# Boost.net
KiCad netlist of a schematic drawn in Altium Designer
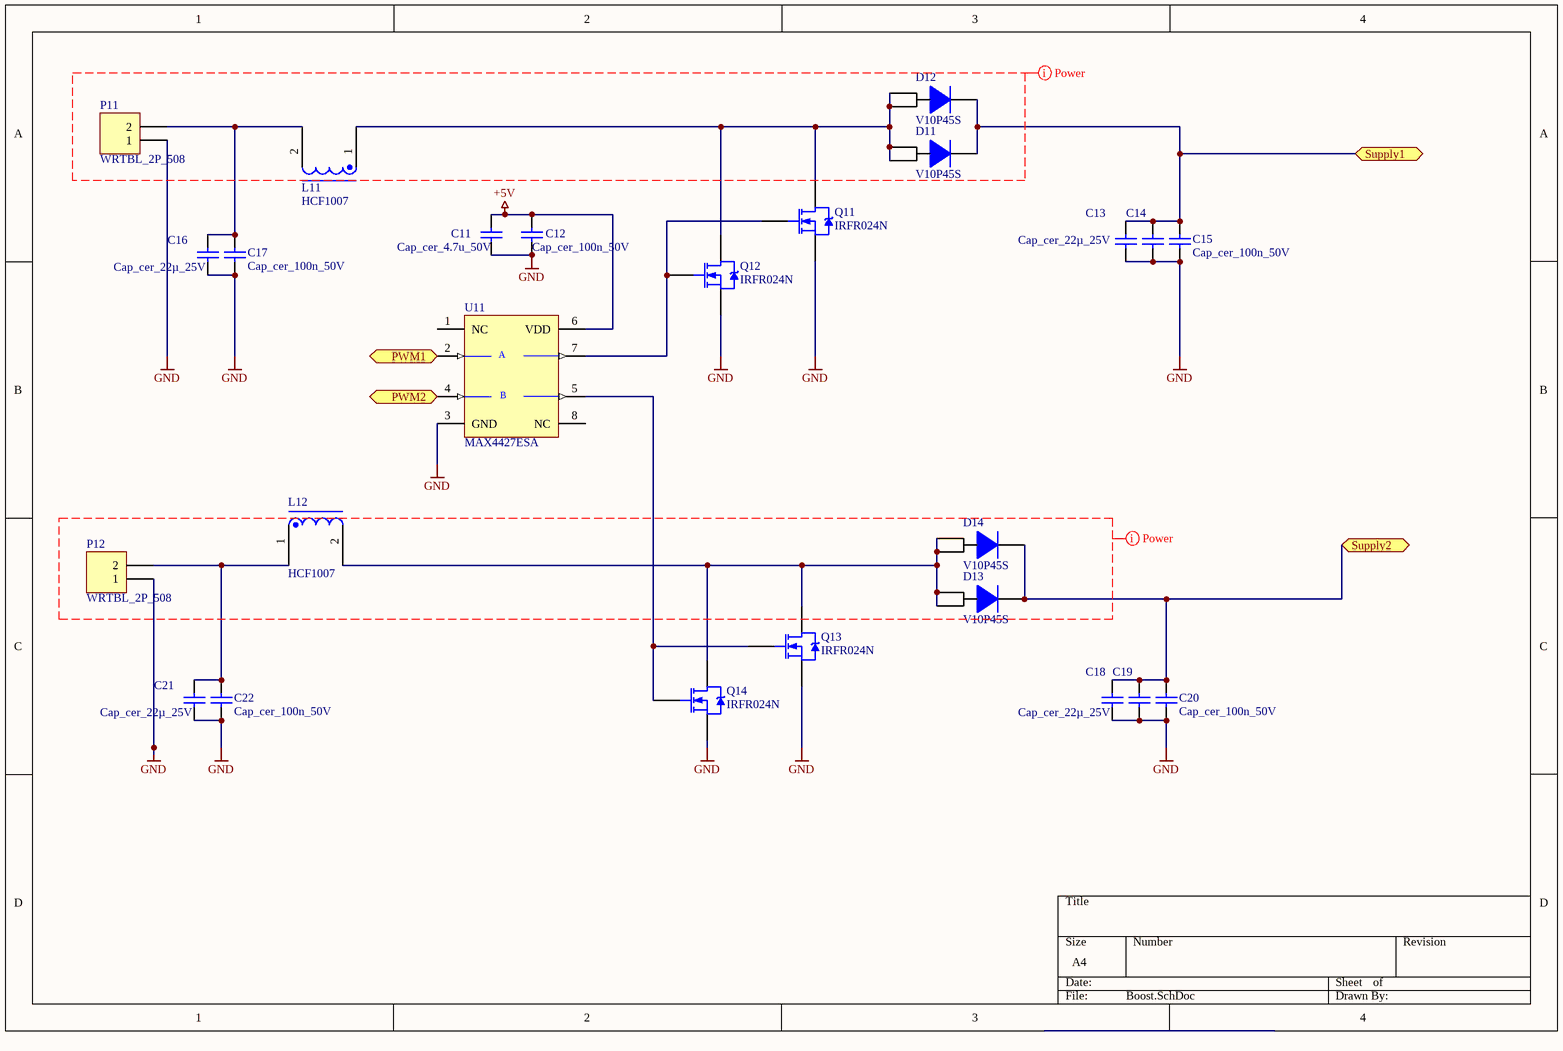
[diagram p0: Boost.SchDoc]

(export (version "E")
  (design (tool "Eeschema 10.0.6"))
  (components
    (comp (ref "C11")
      (value "Cap_cer_4.7u_50V")
      (footprint "_0805")
      (fields (field (name "VOLTAGE") "50V"))
      (libsource (lib "Capacitors$") (part "Cap_124"))
    )
    (comp (ref "C12")
      (value "Cap_cer_100n_50V")
      (footprint "_0805")
      (fields (field (name "VOLTAGE") "50V"))
      (libsource (lib "Capacitors$") (part "Cap_124"))
    )
    (comp (ref "C13")
      (value "~")
      (footprint "_0805")
      (fields (field (name "VOLTAGE") "25V"))
      (libsource (lib "Capacitors$") (part "Cap_124"))
    )
    (comp (ref "C14")
      (value "Cap_cer_22µ_25V")
      (footprint "_0805")
      (fields (field (name "VOLTAGE") "25V"))
      (libsource (lib "Capacitors$") (part "Cap_124"))
    )
    (comp (ref "C15")
      (value "Cap_cer_100n_50V")
      (footprint "_0805")
      (fields (field (name "VOLTAGE") "50V"))
      (libsource (lib "Capacitors$") (part "Cap_124"))
    )
    (comp (ref "C16")
      (value "Cap_cer_22µ_25V")
      (footprint "_0805")
      (fields (field (name "VOLTAGE") "25V"))
      (libsource (lib "Capacitors$") (part "Cap_124"))
    )
    (comp (ref "C17")
      (value "Cap_cer_100n_50V")
      (footprint "_0805")
      (fields (field (name "VOLTAGE") "50V"))
      (libsource (lib "Capacitors$") (part "Cap_124"))
    )
    (comp (ref "C18")
      (value "Cap_cer_22µ_25V")
      (footprint "_0805")
      (fields (field (name "VOLTAGE") "25V"))
      (libsource (lib "Capacitors$") (part "Cap_124"))
    )
    (comp (ref "C19")
      (value "Cap_cer_22µ_25V")
      (footprint "_0805")
      (fields (field (name "VOLTAGE") "25V"))
      (libsource (lib "Capacitors$") (part "Cap_124"))
    )
    (comp (ref "C20")
      (value "Cap_cer_100n_50V")
      (footprint "_0805")
      (fields (field (name "VOLTAGE") "50V"))
      (libsource (lib "Capacitors$") (part "Cap_124"))
    )
    (comp (ref "C21")
      (value "Cap_cer_22µ_25V")
      (footprint "_0805")
      (fields (field (name "VOLTAGE") "25V"))
      (libsource (lib "Capacitors$") (part "Cap_124"))
    )
    (comp (ref "C22")
      (value "Cap_cer_100n_50V")
      (footprint "_0805")
      (fields (field (name "VOLTAGE") "50V"))
      (libsource (lib "Capacitors$") (part "Cap_124"))
    )
    (comp (ref "D11")
      (value "V10P45S")
      (footprint "TO-277A")
      (description "V01P45 Shottky Diode")
      (libsource (lib "Project_Components") (part "V10P45S"))
    )
    (comp (ref "D12")
      (value "V10P45S")
      (footprint "TO-277A")
      (description "V01P45 Shottky Diode")
      (libsource (lib "Project_Components") (part "V10P45S"))
    )
    (comp (ref "D13")
      (value "V10P45S")
      (footprint "TO-277A")
      (description "V01P45 Shottky Diode")
      (libsource (lib "Project_Components") (part "V10P45S"))
    )
    (comp (ref "D14")
      (value "V10P45S")
      (footprint "TO-277A")
      (description "V01P45 Shottky Diode")
      (libsource (lib "Project_Components") (part "V10P45S"))
    )
    (comp (ref "L11")
      (value "HCF1007")
      (footprint "HCF1007")
      (description "HCF1007 Inductor")
      (libsource (lib "Project_Components") (part "HCF1007"))
    )
    (comp (ref "L12")
      (value "HCF1007")
      (footprint "HCF1007")
      (description "HCF1007 Inductor")
      (libsource (lib "Project_Components") (part "HCF1007"))
    )
    (comp (ref "P11")
      (value "WRTBL_2P_508")
      (footprint "WRTBL_2P_508")
      (libsource (lib "Connectors$") (part "Con_7"))
    )
    (comp (ref "P12")
      (value "WRTBL_2P_508")
      (footprint "WRTBL_2P_508")
      (libsource (lib "Connectors$") (part "Con_7"))
    )
    (comp (ref "Q11")
      (value "IRFR024N")
      (footprint "TO-252AA_N")
      (description "HEXFET N-Channel Power MOSFET")
      (fields (field (name "PUBLISHER") "Altium Limited"))
      (libsource (lib "IR Discrete MOSFET - Power") (part "IRFR024N"))
    )
    (comp (ref "Q12")
      (value "IRFR024N")
      (footprint "TO-252AA_N")
      (description "HEXFET N-Channel Power MOSFET")
      (fields (field (name "PUBLISHER") "Altium Limited"))
      (libsource (lib "IR Discrete MOSFET - Power") (part "IRFR024N"))
    )
    (comp (ref "Q13")
      (value "IRFR024N")
      (footprint "TO-252AA_N")
      (description "HEXFET N-Channel Power MOSFET")
      (fields (field (name "PUBLISHER") "Altium Limited"))
      (libsource (lib "IR Discrete MOSFET - Power") (part "IRFR024N"))
    )
    (comp (ref "Q14")
      (value "IRFR024N")
      (footprint "TO-252AA_N")
      (description "HEXFET N-Channel Power MOSFET")
      (fields (field (name "PUBLISHER") "Altium Limited"))
      (libsource (lib "IR Discrete MOSFET - Power") (part "IRFR024N"))
    )
    (comp (ref "U11")
      (value "MAX4427ESA")
      (footprint "NSO8_N")
      (description "Dual High-Speed 1.5A MOSFET Driver")
      (fields (field (name "PUBLISHER") "Altium Limited"))
      (libsource (lib "Maxim Interface MOSFET Driver") (part "MAX4427ESA"))
    )
  )
  (nets
    (net (code "1") (name "+5V") (class "Default")
      (node (ref "C11") (pin "2") (pinfunction "2_2") (pintype "passive"))
      (node (ref "C12") (pin "2") (pinfunction "2_2") (pintype "passive"))
      (node (ref "U11") (pin "6") (pinfunction "VDD_6") (pintype "power_in"))
    )
    (net (code "2") (name "/PWM1") (class "Default")
      (node (ref "U11") (pin "2") (pinfunction "INA_2") (pintype "input"))
    )
    (net (code "3") (name "/PWM2") (class "Default")
      (node (ref "U11") (pin "4") (pinfunction "INB_4") (pintype "input"))
    )
    (net (code "4") (name "/Supply1") (class "Default")
      (node (ref "C13") (pin "2") (pinfunction "2_2") (pintype "passive"))
      (node (ref "C14") (pin "2") (pinfunction "2_2") (pintype "passive"))
      (node (ref "C15") (pin "2") (pinfunction "2_2") (pintype "passive"))
      (node (ref "D11") (pin "K") (pinfunction "K_K") (pintype "passive"))
      (node (ref "D12") (pin "K") (pinfunction "K_K") (pintype "passive"))
    )
    (net (code "5") (name "/Supply2") (class "Default")
      (node (ref "C18") (pin "2") (pinfunction "2_2") (pintype "passive"))
      (node (ref "C19") (pin "2") (pinfunction "2_2") (pintype "passive"))
      (node (ref "C20") (pin "2") (pinfunction "2_2") (pintype "passive"))
      (node (ref "D13") (pin "K") (pinfunction "K_K") (pintype "passive"))
      (node (ref "D14") (pin "K") (pinfunction "K_K") (pintype "passive"))
    )
    (net (code "6") (name "GND") (class "Default")
      (node (ref "C11") (pin "1") (pinfunction "1_1") (pintype "passive"))
      (node (ref "C12") (pin "1") (pinfunction "1_1") (pintype "passive"))
      (node (ref "C13") (pin "1") (pinfunction "1_1") (pintype "passive"))
      (node (ref "C14") (pin "1") (pinfunction "1_1") (pintype "passive"))
      (node (ref "C15") (pin "1") (pinfunction "1_1") (pintype "passive"))
      (node (ref "C16") (pin "1") (pinfunction "1_1") (pintype "passive"))
      (node (ref "C17") (pin "1") (pinfunction "1_1") (pintype "passive"))
      (node (ref "C18") (pin "1") (pinfunction "1_1") (pintype "passive"))
      (node (ref "C19") (pin "1") (pinfunction "1_1") (pintype "passive"))
      (node (ref "C20") (pin "1") (pinfunction "1_1") (pintype "passive"))
      (node (ref "C21") (pin "1") (pinfunction "1_1") (pintype "passive"))
      (node (ref "C22") (pin "1") (pinfunction "1_1") (pintype "passive"))
      (node (ref "P11") (pin "1") (pinfunction "1_1") (pintype "passive"))
      (node (ref "P12") (pin "1") (pinfunction "1_1") (pintype "passive"))
      (node (ref "Q11") (pin "3") (pinfunction "S_3") (pintype "passive"))
      (node (ref "Q12") (pin "3") (pinfunction "S_3") (pintype "passive"))
      (node (ref "Q13") (pin "3") (pinfunction "S_3") (pintype "passive"))
      (node (ref "Q14") (pin "3") (pinfunction "S_3") (pintype "passive"))
      (node (ref "U11") (pin "3") (pinfunction "GND_3") (pintype "power_in"))
    )
    (net (code "7") (name "Net-(C16-Pad2)") (class "Default")
      (node (ref "C16") (pin "2") (pinfunction "2_2") (pintype "passive"))
      (node (ref "C17") (pin "2") (pinfunction "2_2") (pintype "passive"))
      (node (ref "L11") (pin "2") (pinfunction "2_2") (pintype "passive"))
      (node (ref "P11") (pin "2") (pinfunction "2_2") (pintype "passive"))
    )
    (net (code "8") (name "Net-(C21-Pad2)") (class "Default")
      (node (ref "C21") (pin "2") (pinfunction "2_2") (pintype "passive"))
      (node (ref "C22") (pin "2") (pinfunction "2_2") (pintype "passive"))
      (node (ref "L12") (pin "1") (pinfunction "1_1") (pintype "passive"))
      (node (ref "P12") (pin "2") (pinfunction "2_2") (pintype "passive"))
    )
    (net (code "9") (name "Net-(Q11-D)") (class "Default")
      (node (ref "D11") (pin "A1") (pinfunction "A1_A1") (pintype "passive"))
      (node (ref "D11") (pin "A2") (pinfunction "A2_A2") (pintype "passive"))
      (node (ref "D12") (pin "A1") (pinfunction "A1_A1") (pintype "passive"))
      (node (ref "D12") (pin "A2") (pinfunction "A2_A2") (pintype "passive"))
      (node (ref "L11") (pin "1") (pinfunction "1_1") (pintype "passive"))
      (node (ref "Q11") (pin "4") (pinfunction "D_4") (pintype "passive"))
      (node (ref "Q12") (pin "4") (pinfunction "D_4") (pintype "passive"))
    )
    (net (code "10") (name "Net-(Q11-G)") (class "Default")
      (node (ref "Q11") (pin "1") (pinfunction "G_1") (pintype "passive"))
      (node (ref "Q12") (pin "1") (pinfunction "G_1") (pintype "passive"))
      (node (ref "U11") (pin "7") (pinfunction "OUTA_7") (pintype "output"))
    )
    (net (code "11") (name "Net-(Q13-D)") (class "Default")
      (node (ref "D13") (pin "A1") (pinfunction "A1_A1") (pintype "passive"))
      (node (ref "D13") (pin "A2") (pinfunction "A2_A2") (pintype "passive"))
      (node (ref "D14") (pin "A1") (pinfunction "A1_A1") (pintype "passive"))
      (node (ref "D14") (pin "A2") (pinfunction "A2_A2") (pintype "passive"))
      (node (ref "L12") (pin "2") (pinfunction "2_2") (pintype "passive"))
      (node (ref "Q13") (pin "4") (pinfunction "D_4") (pintype "passive"))
      (node (ref "Q14") (pin "4") (pinfunction "D_4") (pintype "passive"))
    )
    (net (code "12") (name "Net-(Q13-G)") (class "Default")
      (node (ref "Q13") (pin "1") (pinfunction "G_1") (pintype "passive"))
      (node (ref "Q14") (pin "1") (pinfunction "G_1") (pintype "passive"))
      (node (ref "U11") (pin "5") (pinfunction "OUTB_5") (pintype "output"))
    )
    (net (code "13") (name "unconnected-(U11-NC-Pad1)") (class "Default")
      (node (ref "U11") (pin "1") (pinfunction "NC_1") (pintype "passive"))
    )
    (net (code "14") (name "unconnected-(U11-NC-Pad8)") (class "Default")
      (node (ref "U11") (pin "8") (pinfunction "NC_8") (pintype "passive"))
    )
  )
)
